# Power_Reg.net
KiCad netlist of a schematic drawn in Altium Designer
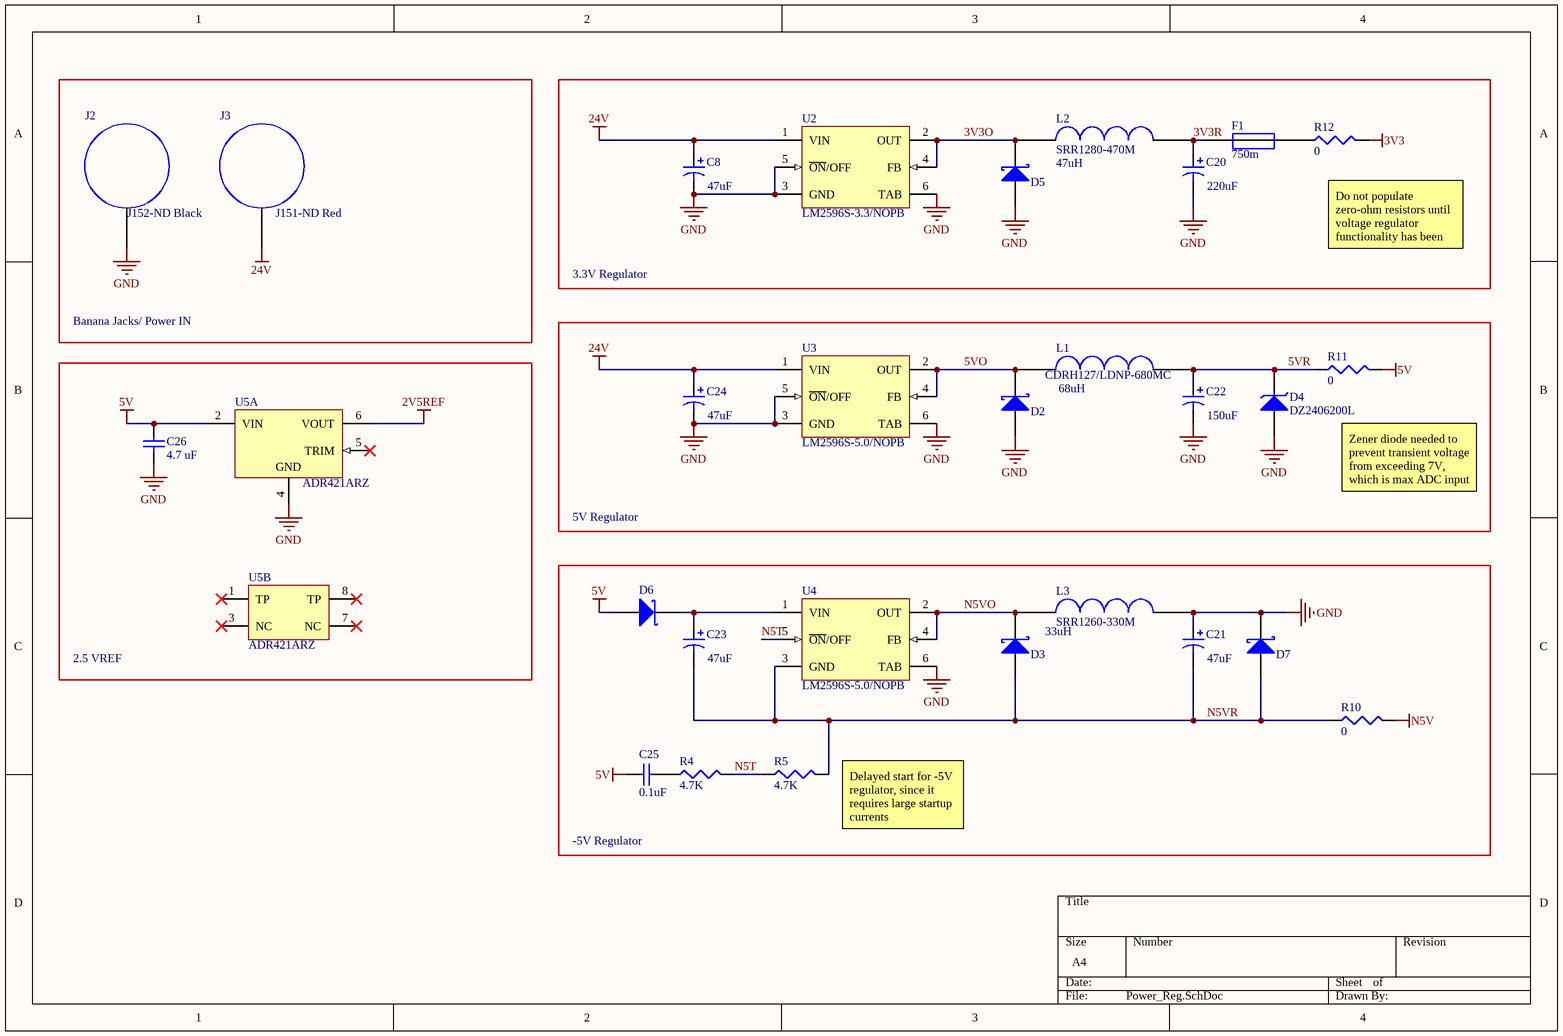
[diagram p0: Power_Reg.SchDoc]

(export (version "E")
  (design (tool "Eeschema 10.0.6"))
  (components
    (comp (ref "C8")
      (value "47uF")
      (footprint "7343")
      (description "CAP TANT 47UF 35V 10% 2917")
      (fields (field (name "Comment") "399-3905-2-ND") (field (name "PUBLISHER") "Altium Limited"))
      (libsource (lib "Vishay Sprague Tantalum Chip Capacitor") (part "CWR11DH476M"))
    )
    (comp (ref "C20")
      (value "220uF")
      (footprint "7343")
      (description "CAP TANT 220uF 16V 10% 2917")
      (fields (field (name "Comment") "399-10429-1-ND") (field (name "PUBLISHER") "Altium Limited"))
      (libsource (lib "Vishay Sprague Tantalum Chip Capacitor") (part "CWR11DH476M"))
    )
    (comp (ref "C21")
      (value "47uF")
      (footprint "7343")
      (description "CAP TANT 47UF 35V 10% 2917")
      (fields (field (name "Comment") "399-3905-2-ND") (field (name "PUBLISHER") "Altium Limited"))
      (libsource (lib "Vishay Sprague Tantalum Chip Capacitor") (part "CWR11DH476M"))
    )
    (comp (ref "C22")
      (value "150uF")
      (footprint "7343")
      (description "CAP TANT 150UF 10V 10% 2917")
      (fields (field (name "Comment") "399-3778-1-ND") (field (name "PUBLISHER") "Altium Limited"))
      (libsource (lib "Vishay Sprague Tantalum Chip Capacitor") (part "CWR11DH476M"))
    )
    (comp (ref "C23")
      (value "47uF")
      (footprint "7343")
      (description "CAP TANT 47UF 35V 10% 2917")
      (fields (field (name "Comment") "399-3905-2-ND") (field (name "PUBLISHER") "Altium Limited"))
      (libsource (lib "Vishay Sprague Tantalum Chip Capacitor") (part "CWR11DH476M"))
    )
    (comp (ref "C24")
      (value "47uF")
      (footprint "7343")
      (description "CAP TANT 47UF 35V 10% 2917")
      (fields (field (name "Comment") "399-3905-2-ND") (field (name "PUBLISHER") "Altium Limited"))
      (libsource (lib "Vishay Sprague Tantalum Chip Capacitor") (part "CWR11DH476M"))
    )
    (comp (ref "C25")
      (value "0.1uF")
      (footprint "0402")
      (description "Ceramic Chip Capacitor - Standard")
      (fields (field (name "Comment") "C0402") (field (name "PUBLISHER") "Altium Limited"))
      (libsource (lib "KEMET Chip Capacitor") (part "C0402"))
    )
    (comp (ref "C26")
      (value "4.7 uF")
      (footprint "0603")
      (description "Ceramic Chip Capacitor - Standard")
      (fields (field (name "Comment") "C0603") (field (name "PUBLISHER") "Altium Limited"))
      (libsource (lib "KEMET Chip Capacitor") (part "C0603"))
    )
    (comp (ref "D2")
      (value "PMEG4050EP,115")
      (footprint "PMEG4050EP,115")
      (description "Schottky Diode, 5A, 40V, SOD-128 Package")
      (libsource (lib "CHIPS_Devices") (part "PMEG4050EP,115"))
    )
    (comp (ref "D3")
      (value "PMEG4050EP,115")
      (footprint "PMEG4050EP,115")
      (description "Schottky Diode, 5A, 40V, SOD-128 Package")
      (libsource (lib "CHIPS_Devices") (part "PMEG4050EP,115"))
    )
    (comp (ref "D4")
      (value "DZ2406200L")
      (footprint "DZ2406200L")
      (description "DIODE ZENER 6.2V 2W TMINIP2. SOD-128")
      (libsource (lib "CHIPS_Devices") (part "DZ2406200L"))
    )
    (comp (ref "D5")
      (value "PMEG4050EP,115")
      (footprint "PMEG4050EP,115")
      (description "Schottky Diode, 5A, 40V, SOD-128 Package")
      (libsource (lib "CHIPS_Devices") (part "PMEG4050EP,115"))
    )
    (comp (ref "D6")
      (value "RSX501L-20TE25")
      (footprint "RSX501L-20TE25")
      (description "DIODE SCHOTTKY 20V 5A PMDS")
      (libsource (lib "CHIPS_Devices") (part "RSX501L-20TE25"))
    )
    (comp (ref "D7")
      (value "PMEG4050EP,115")
      (footprint "PMEG4050EP,115")
      (description "Schottky Diode, 5A, 40V, SOD-128 Package")
      (libsource (lib "CHIPS_Devices") (part "PMEG4050EP,115"))
    )
    (comp (ref "F1")
      (value "750m")
      (footprint "1206")
      (description "FUSE BOARD MNT 750MA 32VAC 63VDC")
      (fields (field (name "Comment") "TR/3216FF750-R"))
      (libsource (lib "CHIPS_Devices") (part "SF-0402F075-2"))
    )
    (comp (ref "J2")
      (value "J152-ND Black")
      (footprint "Banana Jack")
      (description "CONN JACK BANANA INSUL NYLON BLA")
      (libsource (lib "CHIPS_Devices") (part "J-152-ND - Black"))
    )
    (comp (ref "J3")
      (value "J151-ND Red")
      (footprint "Banana Jack")
      (description "CONN JACK BANANA INSUL NYLON RED")
      (libsource (lib "CHIPS_Devices") (part "J151-ND Red"))
    )
    (comp (ref "L1")
      (value "CDRH127/LDNP-680MC")
      (footprint "CDRH127/LDNP-680MC")
      (description "Non-standard package, shielded inductor, 68uH, 2.5A")
      (fields (field (name "ALTIUM_VALUE") "68uH"))
      (libsource (lib "CHIPS_Devices") (part "CDRH127/LDNP-680MC"))
    )
    (comp (ref "L2")
      (value "SRR1280-470M")
      (footprint "SRR1280-470M")
      (description "Non-standard, shielded, 47uH inductor")
      (fields (field (name "ALTIUM_VALUE") "47uH"))
      (libsource (lib "CHIPS_Devices") (part "SRR1280-470M"))
    )
    (comp (ref "L3")
      (value "SRR1260-330M")
      (footprint "SRR1260-330M")
      (description "Non-standard, shielded, inductor, 33uH")
      (fields (field (name "ALTIUM_VALUE") "33uH"))
      (libsource (lib "CHIPS_Devices") (part "SRR1260-330M"))
    )
    (comp (ref "R4")
      (value "4.7K")
      (footprint "J1-0603")
      (description "Resistor")
      (fields (field (name "Comment") "Res3") (field (name "PUBLISHER") "Altium Limited"))
      (libsource (lib "Miscellaneous Devices") (part "Res3"))
    )
    (comp (ref "R5")
      (value "4.7K")
      (footprint "J1-0603")
      (description "Resistor")
      (fields (field (name "Comment") "Res3") (field (name "PUBLISHER") "Altium Limited"))
      (libsource (lib "Miscellaneous Devices") (part "Res3"))
    )
    (comp (ref "R10")
      (value "0")
      (footprint "0805")
      (description "RES SMD 0.0 OHM JUMPER 1/2W 0805")
      (fields (field (name "Comment") "5106") (field (name "PUBLISHER") "Altium Limited"))
      (libsource (lib "CHIPS_Devices") (part "Res3"))
    )
    (comp (ref "R11")
      (value "0")
      (footprint "0805")
      (description "RES SMD 0.0 OHM JUMPER 1/2W 0805")
      (fields (field (name "Comment") "5106") (field (name "PUBLISHER") "Altium Limited"))
      (libsource (lib "CHIPS_Devices") (part "Res3"))
    )
    (comp (ref "R12")
      (value "0")
      (footprint "0805")
      (description "RES SMD 0.0 OHM JUMPER 1/2W 0805")
      (fields (field (name "Comment") "5106") (field (name "PUBLISHER") "Altium Limited"))
      (libsource (lib "CHIPS_Devices") (part "Res3"))
    )
    (comp (ref "U2")
      (value "LM2596S-3.3/NOPB")
      (footprint "TS5B_M")
      (description "SIMPLE SWITCHER® Power Converter 150 KHz 3A Step-Down Voltage Regulator, 5-pin TO-263, Pb-Free")
      (fields (field (name "MANUFACTURER") "National Semiconductor"))
      (libsource (lib "National Semiconductor Switcher") (part "LM2596S-3.3/NOPB"))
    )
    (comp (ref "U3")
      (value "LM2596S-5.0/NOPB")
      (footprint "TS5B_M")
      (description "SIMPLE SWITCHER® Power Converter 150 KHz 3A Step-Down Voltage Regulator, 5-pin TO-263, Pb-Free")
      (fields (field (name "MANUFACTURER") "National Semiconductor"))
      (libsource (lib "National Semiconductor Switcher") (part "LM2596S-5.0/NOPB"))
    )
    (comp (ref "U4")
      (value "LM2596S-5.0/NOPB")
      (footprint "TS5B_N")
      (description "SIMPLE SWITCHER® Power Converter 150 KHz 3A Step-Down Voltage Regulator, 5-pin TO-263, Pb-Free")
      (fields (field (name "MANUFACTURER") "National Semiconductor"))
      (libsource (lib "National Semiconductor Switcher") (part "LM2596S-5.0/NOPB"))
    )
    (comp (ref "U5")
      (value "ADR421ARZ")
      (footprint "ADI-R-8_N")
      (fields (field (name "MANUFACTURER") "Analog Devices"))
      (libsource (lib "Analog Devices Amplifiers and Linear Voltage References") (part "ADR421ARZ"))
    )
  )
  (nets
    (net (code "1") (name "/3V3O") (class "Default")
      (node (ref "D5") (pin "2") (pinfunction "K_2") (pintype "passive"))
      (node (ref "L2") (pin "1") (pinfunction "1_1") (pintype "passive"))
      (node (ref "U2") (pin "2") (pinfunction "OUT_2") (pintype "power_in"))
      (node (ref "U2") (pin "4") (pinfunction "FB_4") (pintype "input"))
    )
    (net (code "2") (name "/3V3R") (class "Default")
      (node (ref "C20") (pin "1") (pinfunction "1_1") (pintype "passive"))
      (node (ref "F1") (pin "1") (pinfunction "1_1") (pintype "passive"))
      (node (ref "L2") (pin "2") (pinfunction "2_2") (pintype "passive"))
    )
    (net (code "3") (name "/5VO") (class "Default")
      (node (ref "D2") (pin "2") (pinfunction "K_2") (pintype "passive"))
      (node (ref "L1") (pin "1") (pinfunction "1_1") (pintype "passive"))
      (node (ref "U3") (pin "2") (pinfunction "OUT_2") (pintype "power_in"))
      (node (ref "U3") (pin "4") (pinfunction "FB_4") (pintype "input"))
    )
    (net (code "4") (name "/5VR") (class "Default")
      (node (ref "C22") (pin "1") (pinfunction "1_1") (pintype "passive"))
      (node (ref "D4") (pin "2") (pinfunction "K_2") (pintype "passive"))
      (node (ref "L1") (pin "2") (pinfunction "2_2") (pintype "passive"))
      (node (ref "R11") (pin "1") (pinfunction "1_1") (pintype "passive"))
    )
    (net (code "5") (name "/N5T") (class "Default")
      (node (ref "R4") (pin "2") (pinfunction "2_2") (pintype "passive"))
      (node (ref "R5") (pin "1") (pinfunction "1_1") (pintype "passive"))
      (node (ref "U4") (pin "5") (pinfunction "~{ON}/OFF_5") (pintype "input"))
    )
    (net (code "6") (name "/N5VO") (class "Default")
      (node (ref "D3") (pin "2") (pinfunction "K_2") (pintype "passive"))
      (node (ref "L3") (pin "1") (pinfunction "1_1") (pintype "passive"))
      (node (ref "U4") (pin "2") (pinfunction "OUT_2") (pintype "power_in"))
      (node (ref "U4") (pin "4") (pinfunction "FB_4") (pintype "input"))
    )
    (net (code "7") (name "/N5VR") (class "Default")
      (node (ref "C21") (pin "2") (pinfunction "2_2") (pintype "passive"))
      (node (ref "C23") (pin "2") (pinfunction "2_2") (pintype "passive"))
      (node (ref "D3") (pin "1") (pinfunction "A_1") (pintype "passive"))
      (node (ref "D7") (pin "1") (pinfunction "A_1") (pintype "passive"))
      (node (ref "R10") (pin "1") (pinfunction "1_1") (pintype "passive"))
      (node (ref "R5") (pin "2") (pinfunction "2_2") (pintype "passive"))
      (node (ref "U4") (pin "3") (pinfunction "GND_3") (pintype "power_in"))
    )
    (net (code "8") (name "2V5REF") (class "Default")
      (node (ref "U5") (pin "6") (pinfunction "VOUT_6") (pintype "power_in"))
    )
    (net (code "9") (name "3V3") (class "Default")
      (node (ref "R12") (pin "2") (pinfunction "2_2") (pintype "passive"))
    )
    (net (code "10") (name "5V") (class "Default")
      (node (ref "C25") (pin "2") (pinfunction "2_2") (pintype "passive"))
      (node (ref "C26") (pin "1") (pinfunction "1_1") (pintype "passive"))
      (node (ref "D6") (pin "1") (pinfunction "A_1") (pintype "passive"))
      (node (ref "R11") (pin "2") (pinfunction "2_2") (pintype "passive"))
      (node (ref "U5") (pin "2") (pinfunction "VIN_2") (pintype "power_in"))
    )
    (net (code "11") (name "24V") (class "Default")
      (node (ref "C24") (pin "1") (pinfunction "1_1") (pintype "passive"))
      (node (ref "C8") (pin "1") (pinfunction "1_1") (pintype "passive"))
      (node (ref "J3") (pin "1") (pinfunction "1_1") (pintype "passive"))
      (node (ref "U2") (pin "1") (pinfunction "VIN_1") (pintype "power_in"))
      (node (ref "U3") (pin "1") (pinfunction "VIN_1") (pintype "power_in"))
    )
    (net (code "12") (name "GND") (class "Default")
      (node (ref "C20") (pin "2") (pinfunction "2_2") (pintype "passive"))
      (node (ref "C21") (pin "1") (pinfunction "1_1") (pintype "passive"))
      (node (ref "C22") (pin "2") (pinfunction "2_2") (pintype "passive"))
      (node (ref "C24") (pin "2") (pinfunction "2_2") (pintype "passive"))
      (node (ref "C26") (pin "2") (pinfunction "2_2") (pintype "passive"))
      (node (ref "C8") (pin "2") (pinfunction "2_2") (pintype "passive"))
      (node (ref "D2") (pin "1") (pinfunction "A_1") (pintype "passive"))
      (node (ref "D4") (pin "1") (pinfunction "A_1") (pintype "passive"))
      (node (ref "D5") (pin "1") (pinfunction "A_1") (pintype "passive"))
      (node (ref "D7") (pin "2") (pinfunction "K_2") (pintype "passive"))
      (node (ref "J2") (pin "1") (pinfunction "1_1") (pintype "passive"))
      (node (ref "L3") (pin "2") (pinfunction "2_2") (pintype "passive"))
      (node (ref "U2") (pin "3") (pinfunction "GND_3") (pintype "power_in"))
      (node (ref "U2") (pin "5") (pinfunction "~{ON}/OFF_5") (pintype "input"))
      (node (ref "U2") (pin "6") (pinfunction "TAB_6") (pintype "power_in"))
      (node (ref "U3") (pin "3") (pinfunction "GND_3") (pintype "power_in"))
      (node (ref "U3") (pin "5") (pinfunction "~{ON}/OFF_5") (pintype "input"))
      (node (ref "U3") (pin "6") (pinfunction "TAB_6") (pintype "power_in"))
      (node (ref "U4") (pin "6") (pinfunction "TAB_6") (pintype "power_in"))
      (node (ref "U5") (pin "4") (pinfunction "GND_4") (pintype "power_in"))
    )
    (net (code "13") (name "N5V") (class "Default")
      (node (ref "R10") (pin "2") (pinfunction "2_2") (pintype "passive"))
    )
    (net (code "14") (name "Net-(C25-Pad1)") (class "Default")
      (node (ref "C25") (pin "1") (pinfunction "1_1") (pintype "passive"))
      (node (ref "R4") (pin "1") (pinfunction "1_1") (pintype "passive"))
    )
    (net (code "15") (name "Net-(D6-K)") (class "Default")
      (node (ref "C23") (pin "1") (pinfunction "1_1") (pintype "passive"))
      (node (ref "D6") (pin "2") (pinfunction "K_2") (pintype "passive"))
      (node (ref "U4") (pin "1") (pinfunction "VIN_1") (pintype "power_in"))
    )
    (net (code "16") (name "Net-(F1-Pad2)") (class "Default")
      (node (ref "F1") (pin "2") (pinfunction "2_2") (pintype "passive"))
      (node (ref "R12") (pin "1") (pinfunction "1_1") (pintype "passive"))
    )
    (net (code "17") (name "unconnected-(U5A-TRIM-Pad5)") (class "Default")
      (node (ref "U5") (pin "5") (pinfunction "TRIM_5") (pintype "input+no_connect"))
    )
    (net (code "18") (name "unconnected-(U5B-NC-Pad3)") (class "Default")
      (node (ref "U5") (pin "3") (pinfunction "NC_3") (pintype "passive+no_connect"))
    )
    (net (code "19") (name "unconnected-(U5B-NC-Pad7)") (class "Default")
      (node (ref "U5") (pin "7") (pinfunction "NC_7") (pintype "passive+no_connect"))
    )
    (net (code "20") (name "unconnected-(U5B-TP-Pad1)") (class "Default")
      (node (ref "U5") (pin "1") (pinfunction "TP_1") (pintype "passive+no_connect"))
    )
    (net (code "21") (name "unconnected-(U5B-TP-Pad8)") (class "Default")
      (node (ref "U5") (pin "8") (pinfunction "TP_8") (pintype "passive+no_connect"))
    )
  )
)
